# k-25m.net
KiCad netlist of a schematic drawn in EAGLE
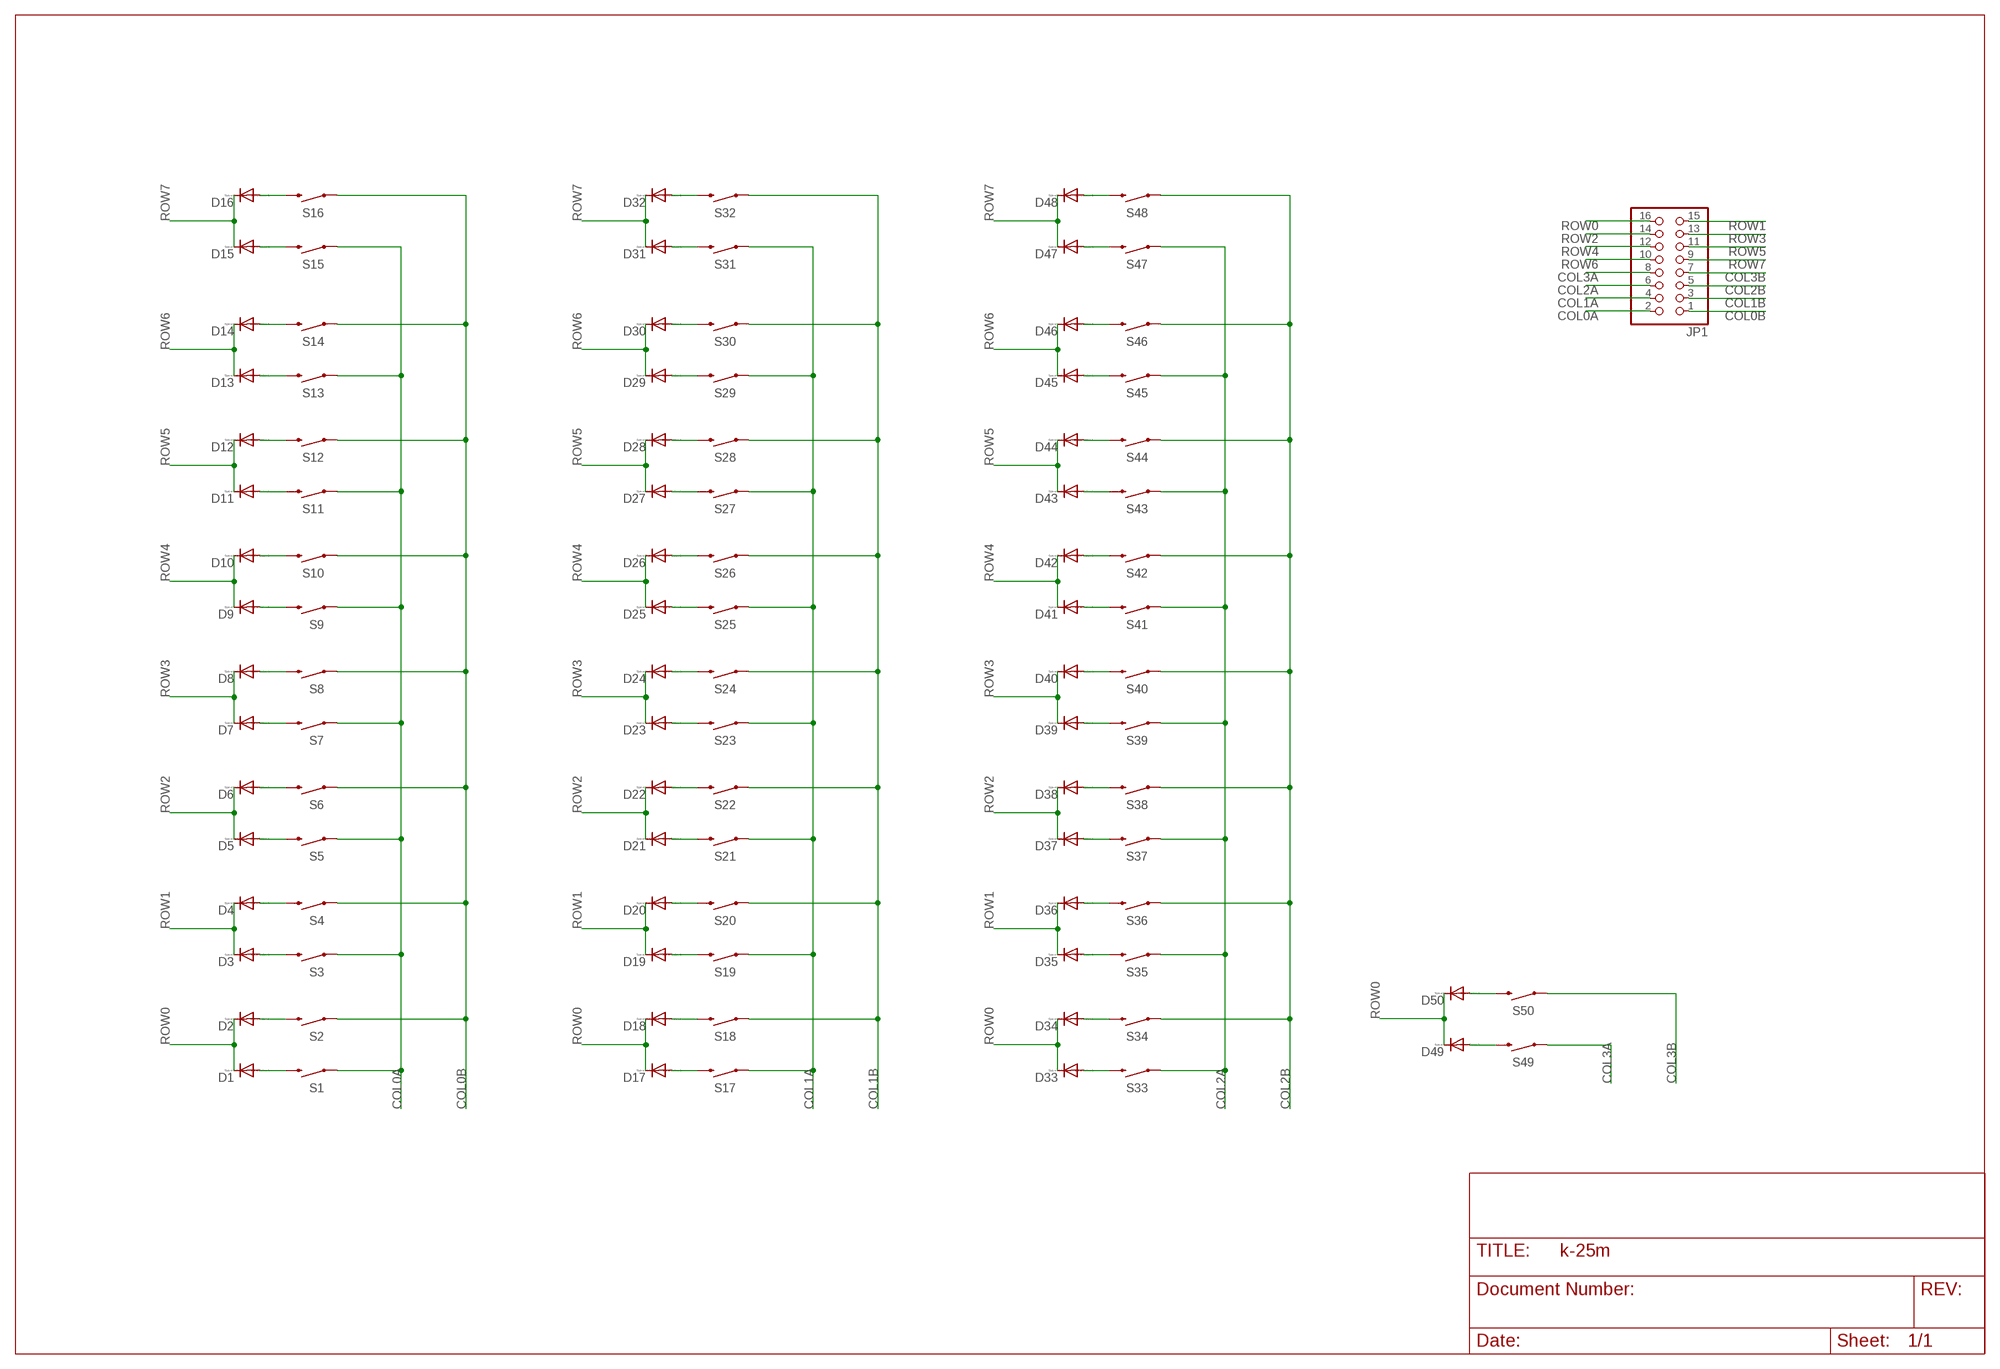
[diagram p0: schematic, sheet 1]

(export (version "E")
  (design (tool "Eeschema 10.0.6"))
  (components
    (comp (ref "D1")
      (value "1N4148DO35-10")
      (footprint "eagle-import:DO35-10")
      (libsource (lib "eagle-import") (part "1N4148DO35-10"))
    )
    (comp (ref "D2")
      (value "1N4148DO35-10")
      (footprint "eagle-import:DO35-10")
      (libsource (lib "eagle-import") (part "1N4148DO35-10"))
    )
    (comp (ref "D3")
      (value "1N4148DO35-10")
      (footprint "eagle-import:DO35-10")
      (libsource (lib "eagle-import") (part "1N4148DO35-10"))
    )
    (comp (ref "D4")
      (value "1N4148DO35-10")
      (footprint "eagle-import:DO35-10")
      (libsource (lib "eagle-import") (part "1N4148DO35-10"))
    )
    (comp (ref "D5")
      (value "1N4148DO35-10")
      (footprint "eagle-import:DO35-10")
      (libsource (lib "eagle-import") (part "1N4148DO35-10"))
    )
    (comp (ref "D6")
      (value "1N4148DO35-10")
      (footprint "eagle-import:DO35-10")
      (libsource (lib "eagle-import") (part "1N4148DO35-10"))
    )
    (comp (ref "D7")
      (value "1N4148DO35-10")
      (footprint "eagle-import:DO35-10")
      (libsource (lib "eagle-import") (part "1N4148DO35-10"))
    )
    (comp (ref "D8")
      (value "1N4148DO35-10")
      (footprint "eagle-import:DO35-10")
      (libsource (lib "eagle-import") (part "1N4148DO35-10"))
    )
    (comp (ref "D9")
      (value "1N4148DO35-10")
      (footprint "eagle-import:DO35-10")
      (libsource (lib "eagle-import") (part "1N4148DO35-10"))
    )
    (comp (ref "D10")
      (value "1N4148DO35-10")
      (footprint "eagle-import:DO35-10")
      (libsource (lib "eagle-import") (part "1N4148DO35-10"))
    )
    (comp (ref "D11")
      (value "1N4148DO35-10")
      (footprint "eagle-import:DO35-10")
      (libsource (lib "eagle-import") (part "1N4148DO35-10"))
    )
    (comp (ref "D12")
      (value "1N4148DO35-10")
      (footprint "eagle-import:DO35-10")
      (libsource (lib "eagle-import") (part "1N4148DO35-10"))
    )
    (comp (ref "D13")
      (value "1N4148DO35-10")
      (footprint "eagle-import:DO35-10")
      (libsource (lib "eagle-import") (part "1N4148DO35-10"))
    )
    (comp (ref "D14")
      (value "1N4148DO35-10")
      (footprint "eagle-import:DO35-10")
      (libsource (lib "eagle-import") (part "1N4148DO35-10"))
    )
    (comp (ref "D15")
      (value "1N4148DO35-10")
      (footprint "eagle-import:DO35-10")
      (libsource (lib "eagle-import") (part "1N4148DO35-10"))
    )
    (comp (ref "D16")
      (value "1N4148DO35-10")
      (footprint "eagle-import:DO35-10")
      (libsource (lib "eagle-import") (part "1N4148DO35-10"))
    )
    (comp (ref "D17")
      (value "1N4148DO35-10")
      (footprint "eagle-import:DO35-10")
      (libsource (lib "eagle-import") (part "1N4148DO35-10"))
    )
    (comp (ref "D18")
      (value "1N4148DO35-10")
      (footprint "eagle-import:DO35-10")
      (libsource (lib "eagle-import") (part "1N4148DO35-10"))
    )
    (comp (ref "D19")
      (value "1N4148DO35-10")
      (footprint "eagle-import:DO35-10")
      (libsource (lib "eagle-import") (part "1N4148DO35-10"))
    )
    (comp (ref "D20")
      (value "1N4148DO35-10")
      (footprint "eagle-import:DO35-10")
      (libsource (lib "eagle-import") (part "1N4148DO35-10"))
    )
    (comp (ref "D21")
      (value "1N4148DO35-10")
      (footprint "eagle-import:DO35-10")
      (libsource (lib "eagle-import") (part "1N4148DO35-10"))
    )
    (comp (ref "D22")
      (value "1N4148DO35-10")
      (footprint "eagle-import:DO35-10")
      (libsource (lib "eagle-import") (part "1N4148DO35-10"))
    )
    (comp (ref "D23")
      (value "1N4148DO35-10")
      (footprint "eagle-import:DO35-10")
      (libsource (lib "eagle-import") (part "1N4148DO35-10"))
    )
    (comp (ref "D24")
      (value "1N4148DO35-10")
      (footprint "eagle-import:DO35-10")
      (libsource (lib "eagle-import") (part "1N4148DO35-10"))
    )
    (comp (ref "D25")
      (value "1N4148DO35-10")
      (footprint "eagle-import:DO35-10")
      (libsource (lib "eagle-import") (part "1N4148DO35-10"))
    )
    (comp (ref "D26")
      (value "1N4148DO35-10")
      (footprint "eagle-import:DO35-10")
      (libsource (lib "eagle-import") (part "1N4148DO35-10"))
    )
    (comp (ref "D27")
      (value "1N4148DO35-10")
      (footprint "eagle-import:DO35-10")
      (libsource (lib "eagle-import") (part "1N4148DO35-10"))
    )
    (comp (ref "D28")
      (value "1N4148DO35-10")
      (footprint "eagle-import:DO35-10")
      (libsource (lib "eagle-import") (part "1N4148DO35-10"))
    )
    (comp (ref "D29")
      (value "1N4148DO35-10")
      (footprint "eagle-import:DO35-10")
      (libsource (lib "eagle-import") (part "1N4148DO35-10"))
    )
    (comp (ref "D30")
      (value "1N4148DO35-10")
      (footprint "eagle-import:DO35-10")
      (libsource (lib "eagle-import") (part "1N4148DO35-10"))
    )
    (comp (ref "D31")
      (value "1N4148DO35-10")
      (footprint "eagle-import:DO35-10")
      (libsource (lib "eagle-import") (part "1N4148DO35-10"))
    )
    (comp (ref "D32")
      (value "1N4148DO35-10")
      (footprint "eagle-import:DO35-10")
      (libsource (lib "eagle-import") (part "1N4148DO35-10"))
    )
    (comp (ref "D33")
      (value "1N4148DO35-10")
      (footprint "eagle-import:DO35-10")
      (libsource (lib "eagle-import") (part "1N4148DO35-10"))
    )
    (comp (ref "D34")
      (value "1N4148DO35-10")
      (footprint "eagle-import:DO35-10")
      (libsource (lib "eagle-import") (part "1N4148DO35-10"))
    )
    (comp (ref "D35")
      (value "1N4148DO35-10")
      (footprint "eagle-import:DO35-10")
      (libsource (lib "eagle-import") (part "1N4148DO35-10"))
    )
    (comp (ref "D36")
      (value "1N4148DO35-10")
      (footprint "eagle-import:DO35-10")
      (libsource (lib "eagle-import") (part "1N4148DO35-10"))
    )
    (comp (ref "D37")
      (value "1N4148DO35-10")
      (footprint "eagle-import:DO35-10")
      (libsource (lib "eagle-import") (part "1N4148DO35-10"))
    )
    (comp (ref "D38")
      (value "1N4148DO35-10")
      (footprint "eagle-import:DO35-10")
      (libsource (lib "eagle-import") (part "1N4148DO35-10"))
    )
    (comp (ref "D39")
      (value "1N4148DO35-10")
      (footprint "eagle-import:DO35-10")
      (libsource (lib "eagle-import") (part "1N4148DO35-10"))
    )
    (comp (ref "D40")
      (value "1N4148DO35-10")
      (footprint "eagle-import:DO35-10")
      (libsource (lib "eagle-import") (part "1N4148DO35-10"))
    )
    (comp (ref "D41")
      (value "1N4148DO35-10")
      (footprint "eagle-import:DO35-10")
      (libsource (lib "eagle-import") (part "1N4148DO35-10"))
    )
    (comp (ref "D42")
      (value "1N4148DO35-10")
      (footprint "eagle-import:DO35-10")
      (libsource (lib "eagle-import") (part "1N4148DO35-10"))
    )
    (comp (ref "D43")
      (value "1N4148DO35-10")
      (footprint "eagle-import:DO35-10")
      (libsource (lib "eagle-import") (part "1N4148DO35-10"))
    )
    (comp (ref "D44")
      (value "1N4148DO35-10")
      (footprint "eagle-import:DO35-10")
      (libsource (lib "eagle-import") (part "1N4148DO35-10"))
    )
    (comp (ref "D45")
      (value "1N4148DO35-10")
      (footprint "eagle-import:DO35-10")
      (libsource (lib "eagle-import") (part "1N4148DO35-10"))
    )
    (comp (ref "D46")
      (value "1N4148DO35-10")
      (footprint "eagle-import:DO35-10")
      (libsource (lib "eagle-import") (part "1N4148DO35-10"))
    )
    (comp (ref "D47")
      (value "1N4148DO35-10")
      (footprint "eagle-import:DO35-10")
      (libsource (lib "eagle-import") (part "1N4148DO35-10"))
    )
    (comp (ref "D48")
      (value "1N4148DO35-10")
      (footprint "eagle-import:DO35-10")
      (libsource (lib "eagle-import") (part "1N4148DO35-10"))
    )
    (comp (ref "D49")
      (value "1N4148DO35-10")
      (footprint "eagle-import:DO35-10")
      (libsource (lib "eagle-import") (part "1N4148DO35-10"))
    )
    (comp (ref "D50")
      (value "1N4148DO35-10")
      (footprint "eagle-import:DO35-10")
      (libsource (lib "eagle-import") (part "1N4148DO35-10"))
    )
    (comp (ref "JP1")
      (value "HEADER-2X8")
      (footprint "eagle-import:2X08")
      (libsource (lib "eagle-import") (part "HEADER-2X8"))
    )
    (comp (ref "S1")
      (value "SWITCHES_-SMD-1101NE")
      (footprint "eagle-import:TACTILE-SWITCH-1101NE")
      (libsource (lib "eagle-import") (part "SWITCHES_-SMD-1101NE"))
    )
    (comp (ref "S2")
      (value "SWITCHES_-SMD-1101NE")
      (footprint "eagle-import:TACTILE-SWITCH-1101NE")
      (libsource (lib "eagle-import") (part "SWITCHES_-SMD-1101NE"))
    )
    (comp (ref "S3")
      (value "SWITCHES_-SMD-1101NE")
      (footprint "eagle-import:TACTILE-SWITCH-1101NE")
      (libsource (lib "eagle-import") (part "SWITCHES_-SMD-1101NE"))
    )
    (comp (ref "S4")
      (value "SWITCHES_-SMD-1101NE")
      (footprint "eagle-import:TACTILE-SWITCH-1101NE")
      (libsource (lib "eagle-import") (part "SWITCHES_-SMD-1101NE"))
    )
    (comp (ref "S5")
      (value "SWITCHES_-SMD-1101NE")
      (footprint "eagle-import:TACTILE-SWITCH-1101NE")
      (libsource (lib "eagle-import") (part "SWITCHES_-SMD-1101NE"))
    )
    (comp (ref "S6")
      (value "SWITCHES_-SMD-1101NE")
      (footprint "eagle-import:TACTILE-SWITCH-1101NE")
      (libsource (lib "eagle-import") (part "SWITCHES_-SMD-1101NE"))
    )
    (comp (ref "S7")
      (value "SWITCHES_-SMD-1101NE")
      (footprint "eagle-import:TACTILE-SWITCH-1101NE")
      (libsource (lib "eagle-import") (part "SWITCHES_-SMD-1101NE"))
    )
    (comp (ref "S8")
      (value "SWITCHES_-SMD-1101NE")
      (footprint "eagle-import:TACTILE-SWITCH-1101NE")
      (libsource (lib "eagle-import") (part "SWITCHES_-SMD-1101NE"))
    )
    (comp (ref "S9")
      (value "SWITCHES_-SMD-1101NE")
      (footprint "eagle-import:TACTILE-SWITCH-1101NE")
      (libsource (lib "eagle-import") (part "SWITCHES_-SMD-1101NE"))
    )
    (comp (ref "S10")
      (value "SWITCHES_-SMD-1101NE")
      (footprint "eagle-import:TACTILE-SWITCH-1101NE")
      (libsource (lib "eagle-import") (part "SWITCHES_-SMD-1101NE"))
    )
    (comp (ref "S11")
      (value "SWITCHES_-SMD-1101NE")
      (footprint "eagle-import:TACTILE-SWITCH-1101NE")
      (libsource (lib "eagle-import") (part "SWITCHES_-SMD-1101NE"))
    )
    (comp (ref "S12")
      (value "SWITCHES_-SMD-1101NE")
      (footprint "eagle-import:TACTILE-SWITCH-1101NE")
      (libsource (lib "eagle-import") (part "SWITCHES_-SMD-1101NE"))
    )
    (comp (ref "S13")
      (value "SWITCHES_-SMD-1101NE")
      (footprint "eagle-import:TACTILE-SWITCH-1101NE")
      (libsource (lib "eagle-import") (part "SWITCHES_-SMD-1101NE"))
    )
    (comp (ref "S14")
      (value "SWITCHES_-SMD-1101NE")
      (footprint "eagle-import:TACTILE-SWITCH-1101NE")
      (libsource (lib "eagle-import") (part "SWITCHES_-SMD-1101NE"))
    )
    (comp (ref "S15")
      (value "SWITCHES_-SMD-1101NE")
      (footprint "eagle-import:TACTILE-SWITCH-1101NE")
      (libsource (lib "eagle-import") (part "SWITCHES_-SMD-1101NE"))
    )
    (comp (ref "S16")
      (value "SWITCHES_-SMD-1101NE")
      (footprint "eagle-import:TACTILE-SWITCH-1101NE")
      (libsource (lib "eagle-import") (part "SWITCHES_-SMD-1101NE"))
    )
    (comp (ref "S17")
      (value "SWITCHES_-SMD-1101NE")
      (footprint "eagle-import:TACTILE-SWITCH-1101NE")
      (libsource (lib "eagle-import") (part "SWITCHES_-SMD-1101NE"))
    )
    (comp (ref "S18")
      (value "SWITCHES_-SMD-1101NE")
      (footprint "eagle-import:TACTILE-SWITCH-1101NE")
      (libsource (lib "eagle-import") (part "SWITCHES_-SMD-1101NE"))
    )
    (comp (ref "S19")
      (value "SWITCHES_-SMD-1101NE")
      (footprint "eagle-import:TACTILE-SWITCH-1101NE")
      (libsource (lib "eagle-import") (part "SWITCHES_-SMD-1101NE"))
    )
    (comp (ref "S20")
      (value "SWITCHES_-SMD-1101NE")
      (footprint "eagle-import:TACTILE-SWITCH-1101NE")
      (libsource (lib "eagle-import") (part "SWITCHES_-SMD-1101NE"))
    )
    (comp (ref "S21")
      (value "SWITCHES_-SMD-1101NE")
      (footprint "eagle-import:TACTILE-SWITCH-1101NE")
      (libsource (lib "eagle-import") (part "SWITCHES_-SMD-1101NE"))
    )
    (comp (ref "S22")
      (value "SWITCHES_-SMD-1101NE")
      (footprint "eagle-import:TACTILE-SWITCH-1101NE")
      (libsource (lib "eagle-import") (part "SWITCHES_-SMD-1101NE"))
    )
    (comp (ref "S23")
      (value "SWITCHES_-SMD-1101NE")
      (footprint "eagle-import:TACTILE-SWITCH-1101NE")
      (libsource (lib "eagle-import") (part "SWITCHES_-SMD-1101NE"))
    )
    (comp (ref "S24")
      (value "SWITCHES_-SMD-1101NE")
      (footprint "eagle-import:TACTILE-SWITCH-1101NE")
      (libsource (lib "eagle-import") (part "SWITCHES_-SMD-1101NE"))
    )
    (comp (ref "S25")
      (value "SWITCHES_-SMD-1101NE")
      (footprint "eagle-import:TACTILE-SWITCH-1101NE")
      (libsource (lib "eagle-import") (part "SWITCHES_-SMD-1101NE"))
    )
    (comp (ref "S26")
      (value "SWITCHES_-SMD-1101NE")
      (footprint "eagle-import:TACTILE-SWITCH-1101NE")
      (libsource (lib "eagle-import") (part "SWITCHES_-SMD-1101NE"))
    )
    (comp (ref "S27")
      (value "SWITCHES_-SMD-1101NE")
      (footprint "eagle-import:TACTILE-SWITCH-1101NE")
      (libsource (lib "eagle-import") (part "SWITCHES_-SMD-1101NE"))
    )
    (comp (ref "S28")
      (value "SWITCHES_-SMD-1101NE")
      (footprint "eagle-import:TACTILE-SWITCH-1101NE")
      (libsource (lib "eagle-import") (part "SWITCHES_-SMD-1101NE"))
    )
    (comp (ref "S29")
      (value "SWITCHES_-SMD-1101NE")
      (footprint "eagle-import:TACTILE-SWITCH-1101NE")
      (libsource (lib "eagle-import") (part "SWITCHES_-SMD-1101NE"))
    )
    (comp (ref "S30")
      (value "SWITCHES_-SMD-1101NE")
      (footprint "eagle-import:TACTILE-SWITCH-1101NE")
      (libsource (lib "eagle-import") (part "SWITCHES_-SMD-1101NE"))
    )
    (comp (ref "S31")
      (value "SWITCHES_-SMD-1101NE")
      (footprint "eagle-import:TACTILE-SWITCH-1101NE")
      (libsource (lib "eagle-import") (part "SWITCHES_-SMD-1101NE"))
    )
    (comp (ref "S32")
      (value "SWITCHES_-SMD-1101NE")
      (footprint "eagle-import:TACTILE-SWITCH-1101NE")
      (libsource (lib "eagle-import") (part "SWITCHES_-SMD-1101NE"))
    )
    (comp (ref "S33")
      (value "SWITCHES_-SMD-1101NE")
      (footprint "eagle-import:TACTILE-SWITCH-1101NE")
      (libsource (lib "eagle-import") (part "SWITCHES_-SMD-1101NE"))
    )
    (comp (ref "S34")
      (value "SWITCHES_-SMD-1101NE")
      (footprint "eagle-import:TACTILE-SWITCH-1101NE")
      (libsource (lib "eagle-import") (part "SWITCHES_-SMD-1101NE"))
    )
    (comp (ref "S35")
      (value "SWITCHES_-SMD-1101NE")
      (footprint "eagle-import:TACTILE-SWITCH-1101NE")
      (libsource (lib "eagle-import") (part "SWITCHES_-SMD-1101NE"))
    )
    (comp (ref "S36")
      (value "SWITCHES_-SMD-1101NE")
      (footprint "eagle-import:TACTILE-SWITCH-1101NE")
      (libsource (lib "eagle-import") (part "SWITCHES_-SMD-1101NE"))
    )
    (comp (ref "S37")
      (value "SWITCHES_-SMD-1101NE")
      (footprint "eagle-import:TACTILE-SWITCH-1101NE")
      (libsource (lib "eagle-import") (part "SWITCHES_-SMD-1101NE"))
    )
    (comp (ref "S38")
      (value "SWITCHES_-SMD-1101NE")
      (footprint "eagle-import:TACTILE-SWITCH-1101NE")
      (libsource (lib "eagle-import") (part "SWITCHES_-SMD-1101NE"))
    )
    (comp (ref "S39")
      (value "SWITCHES_-SMD-1101NE")
      (footprint "eagle-import:TACTILE-SWITCH-1101NE")
      (libsource (lib "eagle-import") (part "SWITCHES_-SMD-1101NE"))
    )
    (comp (ref "S40")
      (value "SWITCHES_-SMD-1101NE")
      (footprint "eagle-import:TACTILE-SWITCH-1101NE")
      (libsource (lib "eagle-import") (part "SWITCHES_-SMD-1101NE"))
    )
    (comp (ref "S41")
      (value "SWITCHES_-SMD-1101NE")
      (footprint "eagle-import:TACTILE-SWITCH-1101NE")
      (libsource (lib "eagle-import") (part "SWITCHES_-SMD-1101NE"))
    )
    (comp (ref "S42")
      (value "SWITCHES_-SMD-1101NE")
      (footprint "eagle-import:TACTILE-SWITCH-1101NE")
      (libsource (lib "eagle-import") (part "SWITCHES_-SMD-1101NE"))
    )
    (comp (ref "S43")
      (value "SWITCHES_-SMD-1101NE")
      (footprint "eagle-import:TACTILE-SWITCH-1101NE")
      (libsource (lib "eagle-import") (part "SWITCHES_-SMD-1101NE"))
    )
    (comp (ref "S44")
      (value "SWITCHES_-SMD-1101NE")
      (footprint "eagle-import:TACTILE-SWITCH-1101NE")
      (libsource (lib "eagle-import") (part "SWITCHES_-SMD-1101NE"))
    )
    (comp (ref "S45")
      (value "SWITCHES_-SMD-1101NE")
      (footprint "eagle-import:TACTILE-SWITCH-1101NE")
      (libsource (lib "eagle-import") (part "SWITCHES_-SMD-1101NE"))
    )
    (comp (ref "S46")
      (value "SWITCHES_-SMD-1101NE")
      (footprint "eagle-import:TACTILE-SWITCH-1101NE")
      (libsource (lib "eagle-import") (part "SWITCHES_-SMD-1101NE"))
    )
    (comp (ref "S47")
      (value "SWITCHES_-SMD-1101NE")
      (footprint "eagle-import:TACTILE-SWITCH-1101NE")
      (libsource (lib "eagle-import") (part "SWITCHES_-SMD-1101NE"))
    )
    (comp (ref "S48")
      (value "SWITCHES_-SMD-1101NE")
      (footprint "eagle-import:TACTILE-SWITCH-1101NE")
      (libsource (lib "eagle-import") (part "SWITCHES_-SMD-1101NE"))
    )
    (comp (ref "S49")
      (value "SWITCHES_-SMD-1101NE")
      (footprint "eagle-import:TACTILE-SWITCH-1101NE")
      (libsource (lib "eagle-import") (part "SWITCHES_-SMD-1101NE"))
    )
    (comp (ref "S50")
      (value "SWITCHES_-SMD-1101NE")
      (footprint "eagle-import:TACTILE-SWITCH-1101NE")
      (libsource (lib "eagle-import") (part "SWITCHES_-SMD-1101NE"))
    )
  )
  (nets
    (net (code "1") (name "/COL0A") (class "Default")
      (node (ref "JP1") (pin "2") (pinfunction "2_2") (pintype "passive"))
      (node (ref "S1") (pin "P$1") (pinfunction "1_P$1") (pintype "passive"))
      (node (ref "S11") (pin "P$1") (pinfunction "1_P$1") (pintype "passive"))
      (node (ref "S13") (pin "P$1") (pinfunction "1_P$1") (pintype "passive"))
      (node (ref "S15") (pin "P$1") (pinfunction "1_P$1") (pintype "passive"))
      (node (ref "S3") (pin "P$1") (pinfunction "1_P$1") (pintype "passive"))
      (node (ref "S5") (pin "P$1") (pinfunction "1_P$1") (pintype "passive"))
      (node (ref "S7") (pin "P$1") (pinfunction "1_P$1") (pintype "passive"))
      (node (ref "S9") (pin "P$1") (pinfunction "1_P$1") (pintype "passive"))
    )
    (net (code "2") (name "/COL0B") (class "Default")
      (node (ref "JP1") (pin "1") (pinfunction "1_1") (pintype "passive"))
      (node (ref "S10") (pin "P$1") (pinfunction "1_P$1") (pintype "passive"))
      (node (ref "S12") (pin "P$1") (pinfunction "1_P$1") (pintype "passive"))
      (node (ref "S14") (pin "P$1") (pinfunction "1_P$1") (pintype "passive"))
      (node (ref "S16") (pin "P$1") (pinfunction "1_P$1") (pintype "passive"))
      (node (ref "S2") (pin "P$1") (pinfunction "1_P$1") (pintype "passive"))
      (node (ref "S4") (pin "P$1") (pinfunction "1_P$1") (pintype "passive"))
      (node (ref "S6") (pin "P$1") (pinfunction "1_P$1") (pintype "passive"))
      (node (ref "S8") (pin "P$1") (pinfunction "1_P$1") (pintype "passive"))
    )
    (net (code "3") (name "/COL1A") (class "Default")
      (node (ref "JP1") (pin "4") (pinfunction "4_4") (pintype "passive"))
      (node (ref "S17") (pin "P$1") (pinfunction "1_P$1") (pintype "passive"))
      (node (ref "S19") (pin "P$1") (pinfunction "1_P$1") (pintype "passive"))
      (node (ref "S21") (pin "P$1") (pinfunction "1_P$1") (pintype "passive"))
      (node (ref "S23") (pin "P$1") (pinfunction "1_P$1") (pintype "passive"))
      (node (ref "S25") (pin "P$1") (pinfunction "1_P$1") (pintype "passive"))
      (node (ref "S27") (pin "P$1") (pinfunction "1_P$1") (pintype "passive"))
      (node (ref "S29") (pin "P$1") (pinfunction "1_P$1") (pintype "passive"))
      (node (ref "S31") (pin "P$1") (pinfunction "1_P$1") (pintype "passive"))
    )
    (net (code "4") (name "/COL1B") (class "Default")
      (node (ref "JP1") (pin "3") (pinfunction "3_3") (pintype "passive"))
      (node (ref "S18") (pin "P$1") (pinfunction "1_P$1") (pintype "passive"))
      (node (ref "S20") (pin "P$1") (pinfunction "1_P$1") (pintype "passive"))
      (node (ref "S22") (pin "P$1") (pinfunction "1_P$1") (pintype "passive"))
      (node (ref "S24") (pin "P$1") (pinfunction "1_P$1") (pintype "passive"))
      (node (ref "S26") (pin "P$1") (pinfunction "1_P$1") (pintype "passive"))
      (node (ref "S28") (pin "P$1") (pinfunction "1_P$1") (pintype "passive"))
      (node (ref "S30") (pin "P$1") (pinfunction "1_P$1") (pintype "passive"))
      (node (ref "S32") (pin "P$1") (pinfunction "1_P$1") (pintype "passive"))
    )
    (net (code "5") (name "/COL2A") (class "Default")
      (node (ref "JP1") (pin "6") (pinfunction "6_6") (pintype "passive"))
      (node (ref "S33") (pin "P$1") (pinfunction "1_P$1") (pintype "passive"))
      (node (ref "S35") (pin "P$1") (pinfunction "1_P$1") (pintype "passive"))
      (node (ref "S37") (pin "P$1") (pinfunction "1_P$1") (pintype "passive"))
      (node (ref "S39") (pin "P$1") (pinfunction "1_P$1") (pintype "passive"))
      (node (ref "S41") (pin "P$1") (pinfunction "1_P$1") (pintype "passive"))
      (node (ref "S43") (pin "P$1") (pinfunction "1_P$1") (pintype "passive"))
      (node (ref "S45") (pin "P$1") (pinfunction "1_P$1") (pintype "passive"))
      (node (ref "S47") (pin "P$1") (pinfunction "1_P$1") (pintype "passive"))
    )
    (net (code "6") (name "/COL2B") (class "Default")
      (node (ref "JP1") (pin "5") (pinfunction "5_5") (pintype "passive"))
      (node (ref "S34") (pin "P$1") (pinfunction "1_P$1") (pintype "passive"))
      (node (ref "S36") (pin "P$1") (pinfunction "1_P$1") (pintype "passive"))
      (node (ref "S38") (pin "P$1") (pinfunction "1_P$1") (pintype "passive"))
      (node (ref "S40") (pin "P$1") (pinfunction "1_P$1") (pintype "passive"))
      (node (ref "S42") (pin "P$1") (pinfunction "1_P$1") (pintype "passive"))
      (node (ref "S44") (pin "P$1") (pinfunction "1_P$1") (pintype "passive"))
      (node (ref "S46") (pin "P$1") (pinfunction "1_P$1") (pintype "passive"))
      (node (ref "S48") (pin "P$1") (pinfunction "1_P$1") (pintype "passive"))
    )
    (net (code "7") (name "/COL3A") (class "Default")
      (node (ref "JP1") (pin "8") (pinfunction "8_8") (pintype "passive"))
      (node (ref "S49") (pin "P$1") (pinfunction "1_P$1") (pintype "passive"))
    )
    (net (code "8") (name "/COL3B") (class "Default")
      (node (ref "JP1") (pin "7") (pinfunction "7_7") (pintype "passive"))
      (node (ref "S50") (pin "P$1") (pinfunction "1_P$1") (pintype "passive"))
    )
    (net (code "9") (name "/ROW0") (class "Default")
      (node (ref "D1") (pin "C") (pinfunction "C_C") (pintype "passive"))
      (node (ref "D17") (pin "C") (pinfunction "C_C") (pintype "passive"))
      (node (ref "D18") (pin "C") (pinfunction "C_C") (pintype "passive"))
      (node (ref "D2") (pin "C") (pinfunction "C_C") (pintype "passive"))
      (node (ref "D33") (pin "C") (pinfunction "C_C") (pintype "passive"))
      (node (ref "D34") (pin "C") (pinfunction "C_C") (pintype "passive"))
      (node (ref "D49") (pin "C") (pinfunction "C_C") (pintype "passive"))
      (node (ref "D50") (pin "C") (pinfunction "C_C") (pintype "passive"))
      (node (ref "JP1") (pin "16") (pinfunction "16_16") (pintype "passive"))
    )
    (net (code "10") (name "/ROW1") (class "Default")
      (node (ref "D19") (pin "C") (pinfunction "C_C") (pintype "passive"))
      (node (ref "D20") (pin "C") (pinfunction "C_C") (pintype "passive"))
      (node (ref "D3") (pin "C") (pinfunction "C_C") (pintype "passive"))
      (node (ref "D35") (pin "C") (pinfunction "C_C") (pintype "passive"))
      (node (ref "D36") (pin "C") (pinfunction "C_C") (pintype "passive"))
      (node (ref "D4") (pin "C") (pinfunction "C_C") (pintype "passive"))
      (node (ref "JP1") (pin "15") (pinfunction "15_15") (pintype "passive"))
    )
    (net (code "11") (name "/ROW2") (class "Default")
      (node (ref "D21") (pin "C") (pinfunction "C_C") (pintype "passive"))
      (node (ref "D22") (pin "C") (pinfunction "C_C") (pintype "passive"))
      (node (ref "D37") (pin "C") (pinfunction "C_C") (pintype "passive"))
      (node (ref "D38") (pin "C") (pinfunction "C_C") (pintype "passive"))
      (node (ref "D5") (pin "C") (pinfunction "C_C") (pintype "passive"))
      (node (ref "D6") (pin "C") (pinfunction "C_C") (pintype "passive"))
      (node (ref "JP1") (pin "14") (pinfunction "14_14") (pintype "passive"))
    )
    (net (code "12") (name "/ROW3") (class "Default")
      (node (ref "D23") (pin "C") (pinfunction "C_C") (pintype "passive"))
      (node (ref "D24") (pin "C") (pinfunction "C_C") (pintype "passive"))
      (node (ref "D39") (pin "C") (pinfunction "C_C") (pintype "passive"))
      (node (ref "D40") (pin "C") (pinfunction "C_C") (pintype "passive"))
      (node (ref "D7") (pin "C") (pinfunction "C_C") (pintype "passive"))
      (node (ref "D8") (pin "C") (pinfunction "C_C") (pintype "passive"))
      (node (ref "JP1") (pin "13") (pinfunction "13_13") (pintype "passive"))
    )
    (net (code "13") (name "/ROW4") (class "Default")
      (node (ref "D10") (pin "C") (pinfunction "C_C") (pintype "passive"))
      (node (ref "D25") (pin "C") (pinfunction "C_C") (pintype "passive"))
      (node (ref "D26") (pin "C") (pinfunction "C_C") (pintype "passive"))
      (node (ref "D41") (pin "C") (pinfunction "C_C") (pintype "passive"))
      (node (ref "D42") (pin "C") (pinfunction "C_C") (pintype "passive"))
      (node (ref "D9") (pin "C") (pinfunction "C_C") (pintype "passive"))
      (node (ref "JP1") (pin "12") (pinfunction "12_12") (pintype "passive"))
    )
    (net (code "14") (name "/ROW5") (class "Default")
      (node (ref "D11") (pin "C") (pinfunction "C_C") (pintype "passive"))
      (node (ref "D12") (pin "C") (pinfunction "C_C") (pintype "passive"))
      (node (ref "D27") (pin "C") (pinfunction "C_C") (pintype "passive"))
      (node (ref "D28") (pin "C") (pinfunction "C_C") (pintype "passive"))
      (node (ref "D43") (pin "C") (pinfunction "C_C") (pintype "passive"))
      (node (ref "D44") (pin "C") (pinfunction "C_C") (pintype "passive"))
      (node (ref "JP1") (pin "11") (pinfunction "11_11") (pintype "passive"))
    )
    (net (code "15") (name "/ROW6") (class "Default")
      (node (ref "D13") (pin "C") (pinfunction "C_C") (pintype "passive"))
      (node (ref "D14") (pin "C") (pinfunction "C_C") (pintype "passive"))
      (node (ref "D29") (pin "C") (pinfunction "C_C") (pintype "passive"))
      (node (ref "D30") (pin "C") (pinfunction "C_C") (pintype "passive"))
      (node (ref "D45") (pin "C") (pinfunction "C_C") (pintype "passive"))
      (node (ref "D46") (pin "C") (pinfunction "C_C") (pintype "passive"))
      (node (ref "JP1") (pin "10") (pinfunction "10_10") (pintype "passive"))
    )
    (net (code "16") (name "/ROW7") (class "Default")
      (node (ref "D15") (pin "C") (pinfunction "C_C") (pintype "passive"))
      (node (ref "D16") (pin "C") (pinfunction "C_C") (pintype "passive"))
      (node (ref "D31") (pin "C") (pinfunction "C_C") (pintype "passive"))
      (node (ref "D32") (pin "C") (pinfunction "C_C") (pintype "passive"))
      (node (ref "D47") (pin "C") (pinfunction "C_C") (pintype "passive"))
      (node (ref "D48") (pin "C") (pinfunction "C_C") (pintype "passive"))
      (node (ref "JP1") (pin "9") (pinfunction "9_9") (pintype "passive"))
    )
    (net (code "17") (name "Net-(S1-2)") (class "Default")
      (node (ref "D1") (pin "A") (pinfunction "A_A") (pintype "passive"))
      (node (ref "S1") (pin "P$2") (pinfunction "2_P$2") (pintype "passive"))
    )
    (net (code "18") (name "Net-(S2-2)") (class "Default")
      (node (ref "D2") (pin "A") (pinfunction "A_A") (pintype "passive"))
      (node (ref "S2") (pin "P$2") (pinfunction "2_P$2") (pintype "passive"))
    )
    (net (code "19") (name "Net-(S3-2)") (class "Default")
      (node (ref "D3") (pin "A") (pinfunction "A_A") (pintype "passive"))
      (node (ref "S3") (pin "P$2") (pinfunction "2_P$2") (pintype "passive"))
    )
    (net (code "20") (name "Net-(S4-2)") (class "Default")
      (node (ref "D4") (pin "A") (pinfunction "A_A") (pintype "passive"))
      (node (ref "S4") (pin "P$2") (pinfunction "2_P$2") (pintype "passive"))
    )
    (net (code "21") (name "Net-(S5-2)") (class "Default")
      (node (ref "D5") (pin "A") (pinfunction "A_A") (pintype "passive"))
      (node (ref "S5") (pin "P$2") (pinfunction "2_P$2") (pintype "passive"))
    )
    (net (code "22") (name "Net-(S6-2)") (class "Default")
      (node (ref "D6") (pin "A") (pinfunction "A_A") (pintype "passive"))
      (node (ref "S6") (pin "P$2") (pinfunction "2_P$2") (pintype "passive"))
    )
    (net (code "23") (name "Net-(S7-2)") (class "Default")
      (node (ref "D7") (pin "A") (pinfunction "A_A") (pintype "passive"))
      (node (ref "S7") (pin "P$2") (pinfunction "2_P$2") (pintype "passive"))
    )
    (net (code "24") (name "Net-(S8-2)") (class "Default")
      (node (ref "D8") (pin "A") (pinfunction "A_A") (pintype "passive"))
      (node (ref "S8") (pin "P$2") (pinfunction "2_P$2") (pintype "passive"))
    )
    (net (code "25") (name "Net-(S9-2)") (class "Default")
      (node (ref "D9") (pin "A") (pinfunction "A_A") (pintype "passive"))
      (node (ref "S9") (pin "P$2") (pinfunction "2_P$2") (pintype "passive"))
    )
    (net (code "26") (name "Net-(S10-2)") (class "Default")
      (node (ref "D10") (pin "A") (pinfunction "A_A") (pintype "passive"))
      (node (ref "S10") (pin "P$2") (pinfunction "2_P$2") (pintype "passive"))
    )
    (net (code "27") (name "Net-(S11-2)") (class "Default")
      (node (ref "D11") (pin "A") (pinfunction "A_A") (pintype "passive"))
      (node (ref "S11") (pin "P$2") (pinfunction "2_P$2") (pintype "passive"))
    )
    (net (code "28") (name "Net-(S12-2)") (class "Default")
      (node (ref "D12") (pin "A") (pinfunction "A_A") (pintype "passive"))
      (node (ref "S12") (pin "P$2") (pinfunction "2_P$2") (pintype "passive"))
    )
    (net (code "29") (name "Net-(S13-2)") (class "Default")
      (node (ref "D13") (pin "A") (pinfunction "A_A") (pintype "passive"))
      (node (ref "S13") (pin "P$2") (pinfunction "2_P$2") (pintype "passive"))
    )
    (net (code "30") (name "Net-(S14-2)") (class "Default")
      (node (ref "D14") (pin "A") (pinfunction "A_A") (pintype "passive"))
      (node (ref "S14") (pin "P$2") (pinfunction "2_P$2") (pintype "passive"))
    )
    (net (code "31") (name "Net-(S15-2)") (class "Default")
      (node (ref "D15") (pin "A") (pinfunction "A_A") (pintype "passive"))
      (node (ref "S15") (pin "P$2") (pinfunction "2_P$2") (pintype "passive"))
    )
    (net (code "32") (name "Net-(S16-2)") (class "Default")
      (node (ref "D16") (pin "A") (pinfunction "A_A") (pintype "passive"))
      (node (ref "S16") (pin "P$2") (pinfunction "2_P$2") (pintype "passive"))
    )
    (net (code "33") (name "Net-(S17-2)") (class "Default")
      (node (ref "D17") (pin "A") (pinfunction "A_A") (pintype "passive"))
      (node (ref "S17") (pin "P$2") (pinfunction "2_P$2") (pintype "passive"))
    )
    (net (code "34") (name "Net-(S18-2)") (class "Default")
      (node (ref "D18") (pin "A") (pinfunction "A_A") (pintype "passive"))
      (node (ref "S18") (pin "P$2") (pinfunction "2_P$2") (pintype "passive"))
    )
    (net (code "35") (name "Net-(S19-2)") (class "Default")
      (node (ref "D19") (pin "A") (pinfunction "A_A") (pintype "passive"))
      (node (ref "S19") (pin "P$2") (pinfunction "2_P$2") (pintype "passive"))
    )
    (net (code "36") (name "Net-(S20-2)") (class "Default")
      (node (ref "D20") (pin "A") (pinfunction "A_A") (pintype "passive"))
      (node (ref "S20") (pin "P$2") (pinfunction "2_P$2") (pintype "passive"))
    )
    (net (code "37") (name "Net-(S21-2)") (class "Default")
      (node (ref "D21") (pin "A") (pinfunction "A_A") (pintype "passive"))
      (node (ref "S21") (pin "P$2") (pinfunction "2_P$2") (pintype "passive"))
    )
    (net (code "38") (name "Net-(S22-2)") (class "Default")
      (node (ref "D22") (pin "A") (pinfunction "A_A") (pintype "passive"))
      (node (ref "S22") (pin "P$2") (pinfunction "2_P$2") (pintype "passive"))
    )
    (net (code "39") (name "Net-(S23-2)") (class "Default")
      (node (ref "D23") (pin "A") (pinfunction "A_A") (pintype "passive"))
      (node (ref "S23") (pin "P$2") (pinfunction "2_P$2") (pintype "passive"))
    )
    (net (code "40") (name "Net-(S24-2)") (class "Default")
      (node (ref "D24") (pin "A") (pinfunction "A_A") (pintype "passive"))
      (node (ref "S24") (pin "P$2") (pinfunction "2_P$2") (pintype "passive"))
    )
    (net (code "41") (name "Net-(S25-2)") (class "Default")
      (node (ref "D25") (pin "A") (pinfunction "A_A") (pintype "passive"))
      (node (ref "S25") (pin "P$2") (pinfunction "2_P$2") (pintype "passive"))
    )
    (net (code "42") (name "Net-(S26-2)") (class "Default")
      (node (ref "D26") (pin "A") (pinfunction "A_A") (pintype "passive"))
      (node (ref "S26") (pin "P$2") (pinfunction "2_P$2") (pintype "passive"))
    )
    (net (code "43") (name "Net-(S27-2)") (class "Default")
      (node (ref "D27") (pin "A") (pinfunction "A_A") (pintype "passive"))
      (node (ref "S27") (pin "P$2") (pinfunction "2_P$2") (pintype "passive"))
    )
    (net (code "44") (name "Net-(S28-2)") (class "Default")
      (node (ref "D28") (pin "A") (pinfunction "A_A") (pintype "passive"))
      (node (ref "S28") (pin "P$2") (pinfunction "2_P$2") (pintype "passive"))
    )
    (net (code "45") (name "Net-(S29-2)") (class "Default")
      (node (ref "D29") (pin "A") (pinfunction "A_A") (pintype "passive"))
      (node (ref "S29") (pin "P$2") (pinfunction "2_P$2") (pintype "passive"))
    )
    (net (code "46") (name "Net-(S30-2)") (class "Default")
      (node (ref "D30") (pin "A") (pinfunction "A_A") (pintype "passive"))
      (node (ref "S30") (pin "P$2") (pinfunction "2_P$2") (pintype "passive"))
    )
    (net (code "47") (name "Net-(S31-2)") (class "Default")
      (node (ref "D31") (pin "A") (pinfunction "A_A") (pintype "passive"))
      (node (ref "S31") (pin "P$2") (pinfunction "2_P$2") (pintype "passive"))
    )
    (net (code "48") (name "Net-(S32-2)") (class "Default")
      (node (ref "D32") (pin "A") (pinfunction "A_A") (pintype "passive"))
      (node (ref "S32") (pin "P$2") (pinfunction "2_P$2") (pintype "passive"))
    )
    (net (code "49") (name "Net-(S33-2)") (class "Default")
      (node (ref "D33") (pin "A") (pinfunction "A_A") (pintype "passive"))
      (node (ref "S33") (pin "P$2") (pinfunction "2_P$2") (pintype "passive"))
    )
    (net (code "50") (name "Net-(S34-2)") (class "Default")
      (node (ref "D34") (pin "A") (pinfunction "A_A") (pintype "passive"))
      (node (ref "S34") (pin "P$2") (pinfunction "2_P$2") (pintype "passive"))
    )
    (net (code "51") (name "Net-(S35-2)") (class "Default")
      (node (ref "D35") (pin "A") (pinfunction "A_A") (pintype "passive"))
      (node (ref "S35") (pin "P$2") (pinfunction "2_P$2") (pintype "passive"))
    )
    (net (code "52") (name "Net-(S36-2)") (class "Default")
      (node (ref "D36") (pin "A") (pinfunction "A_A") (pintype "passive"))
      (node (ref "S36") (pin "P$2") (pinfunction "2_P$2") (pintype "passive"))
    )
    (net (code "53") (name "Net-(S37-2)") (class "Default")
      (node (ref "D37") (pin "A") (pinfunction "A_A") (pintype "passive"))
      (node (ref "S37") (pin "P$2") (pinfunction "2_P$2") (pintype "passive"))
    )
    (net (code "54") (name "Net-(S38-2)") (class "Default")
      (node (ref "D38") (pin "A") (pinfunction "A_A") (pintype "passive"))
      (node (ref "S38") (pin "P$2") (pinfunction "2_P$2") (pintype "passive"))
    )
    (net (code "55") (name "Net-(S39-2)") (class "Default")
      (node (ref "D39") (pin "A") (pinfunction "A_A") (pintype "passive"))
      (node (ref "S39") (pin "P$2") (pinfunction "2_P$2") (pintype "passive"))
    )
    (net (code "56") (name "Net-(S40-2)") (class "Default")
      (node (ref "D40") (pin "A") (pinfunction "A_A") (pintype "passive"))
      (node (ref "S40") (pin "P$2") (pinfunction "2_P$2") (pintype "passive"))
    )
    (net (code "57") (name "Net-(S41-2)") (class "Default")
      (node (ref "D41") (pin "A") (pinfunction "A_A") (pintype "passive"))
      (node (ref "S41") (pin "P$2") (pinfunction "2_P$2") (pintype "passive"))
    )
    (net (code "58") (name "Net-(S42-2)") (class "Default")
      (node (ref "D42") (pin "A") (pinfunction "A_A") (pintype "passive"))
      (node (ref "S42") (pin "P$2") (pinfunction "2_P$2") (pintype "passive"))
    )
    (net (code "59") (name "Net-(S43-2)") (class "Default")
      (node (ref "D43") (pin "A") (pinfunction "A_A") (pintype "passive"))
      (node (ref "S43") (pin "P$2") (pinfunction "2_P$2") (pintype "passive"))
    )
    (net (code "60") (name "Net-(S44-2)") (class "Default")
      (node (ref "D44") (pin "A") (pinfunction "A_A") (pintype "passive"))
      (node (ref "S44") (pin "P$2") (pinfunction "2_P$2") (pintype "passive"))
    )
    (net (code "61") (name "Net-(S45-2)") (class "Default")
      (node (ref "D45") (pin "A") (pinfunction "A_A") (pintype "passive"))
      (node (ref "S45") (pin "P$2") (pinfunction "2_P$2") (pintype "passive"))
    )
    (net (code "62") (name "Net-(S46-2)") (class "Default")
      (node (ref "D46") (pin "A") (pinfunction "A_A") (pintype "passive"))
      (node (ref "S46") (pin "P$2") (pinfunction "2_P$2") (pintype "passive"))
    )
    (net (code "63") (name "Net-(S47-2)") (class "Default")
      (node (ref "D47") (pin "A") (pinfunction "A_A") (pintype "passive"))
      (node (ref "S47") (pin "P$2") (pinfunction "2_P$2") (pintype "passive"))
    )
    (net (code "64") (name "Net-(S48-2)") (class "Default")
      (node (ref "D48") (pin "A") (pinfunction "A_A") (pintype "passive"))
      (node (ref "S48") (pin "P$2") (pinfunction "2_P$2") (pintype "passive"))
    )
    (net (code "65") (name "Net-(S49-2)") (class "Default")
      (node (ref "D49") (pin "A") (pinfunction "A_A") (pintype "passive"))
      (node (ref "S49") (pin "P$2") (pinfunction "2_P$2") (pintype "passive"))
    )
    (net (code "66") (name "Net-(S50-2)") (class "Default")
      (node (ref "D50") (pin "A") (pinfunction "A_A") (pintype "passive"))
      (node (ref "S50") (pin "P$2") (pinfunction "2_P$2") (pintype "passive"))
    )
  )
)
